# Power_Supply.net
KiCad netlist of a schematic drawn in Altium Designer
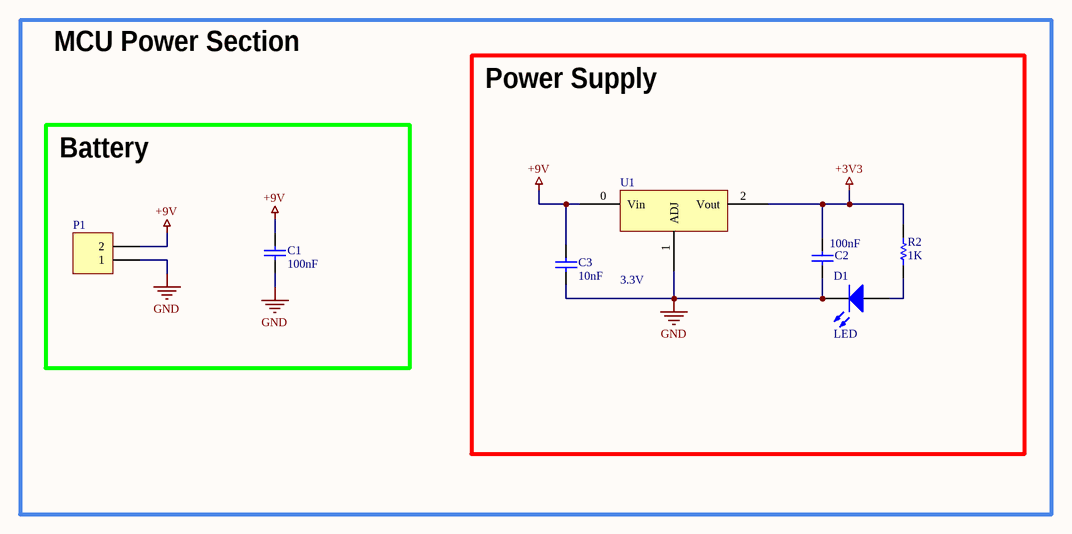
[diagram p0: Power Supply.SchDoc]

(export (version "E")
  (design (tool "Eeschema 10.0.6"))
  (components
    (comp (ref "C1")
      (value "100nF")
      (footprint "C1206")
      (description "Capacitor (Semiconductor SIM Model)")
      (fields (field (name "Comment") "Cap Semi Tantalium") (field (name "PUBLISHER") "Altium Limited"))
      (libsource (lib "Miscellaneous Devices") (part "Cap Semi"))
    )
    (comp (ref "C2")
      (value "100nF")
      (footprint "C1206")
      (description "Capacitor (Semiconductor SIM Model)")
      (fields (field (name "Comment") "Cap Semi Tantalium") (field (name "PUBLISHER") "Altium Limited"))
      (libsource (lib "Miscellaneous Devices") (part "Cap Semi"))
    )
    (comp (ref "C3")
      (value "10nF")
      (footprint "C1206")
      (description "Capacitor (Semiconductor SIM Model)")
      (fields (field (name "Comment") "Cap Semi Tantalium") (field (name "PUBLISHER") "Altium Limited"))
      (libsource (lib "Miscellaneous Devices") (part "Cap Semi"))
    )
    (comp (ref "D1")
      (value "LED")
      (footprint "MY_LED_0805")
      (description "Typical INFRARED GaAs LED")
      (fields (field (name "ASID PART NUMBER") "LED-AS"))
      (libsource (lib "Mylib+Rev+4") (part "LED"))
    )
    (comp (ref "P1")
      (value "~")
      (footprint "HDR1X2H")
      (description "Header, 2-Pin, Right Angle")
      (fields (field (name "VOLTAGE") "9V") (field (name "PUBLISHER") "Altium Limited"))
      (libsource (lib "mculib_Real") (part "Header 2H"))
    )
    (comp (ref "R2")
      (value "1K")
      (footprint "MY_0805")
      (description "Standard resistor")
      (fields (field (name "ASID PART NUMBER") "Res-AS"))
      (libsource (lib "Mylib+Rev+4") (part "Res"))
    )
    (comp (ref "U1")
      (value "LM1117 800-mA, Low-Dropout Linear Regulator")
      (footprint "4-PIN SOT")
      (fields (field (name "OUTPUT VOLTAGE") "3.3V"))
      (libsource (lib "MCU Chip") (part "LM1117"))
    )
  )
  (nets
    (net (code "1") (name "+3V3") (class "Default")
      (node (ref "C2") (pin "2") (pinfunction "2_2") (pintype "passive"))
      (node (ref "R2") (pin "1") (pinfunction "1_1") (pintype "passive"))
      (node (ref "U1") (pin "2") (pinfunction "Vout_2") (pintype "passive"))
    )
    (net (code "2") (name "+9V") (class "Default")
      (node (ref "C1") (pin "2") (pinfunction "2_2") (pintype "passive"))
      (node (ref "C3") (pin "2") (pinfunction "2_2") (pintype "passive"))
      (node (ref "P1") (pin "2") (pinfunction "2_2") (pintype "passive"))
      (node (ref "U1") (pin "0") (pinfunction "Vin_0") (pintype "passive"))
    )
    (net (code "3") (name "GND") (class "Default")
      (node (ref "C1") (pin "1") (pinfunction "1_1") (pintype "passive"))
      (node (ref "C2") (pin "1") (pinfunction "1_1") (pintype "passive"))
      (node (ref "C3") (pin "1") (pinfunction "1_1") (pintype "passive"))
      (node (ref "D1") (pin "K") (pinfunction "K_K") (pintype "passive"))
      (node (ref "P1") (pin "1") (pinfunction "1_1") (pintype "passive"))
      (node (ref "U1") (pin "1") (pinfunction "ADJ_1") (pintype "passive"))
    )
    (net (code "4") (name "Net-(D1-PadA)") (class "Default")
      (node (ref "D1") (pin "A") (pinfunction "A_A") (pintype "passive"))
      (node (ref "R2") (pin "2") (pinfunction "2_2") (pintype "passive"))
    )
  )
)
